# ProProject_2024__Wang01_2024-08-05.net
KiCad netlist of a schematic drawn in EasyEDA Pro
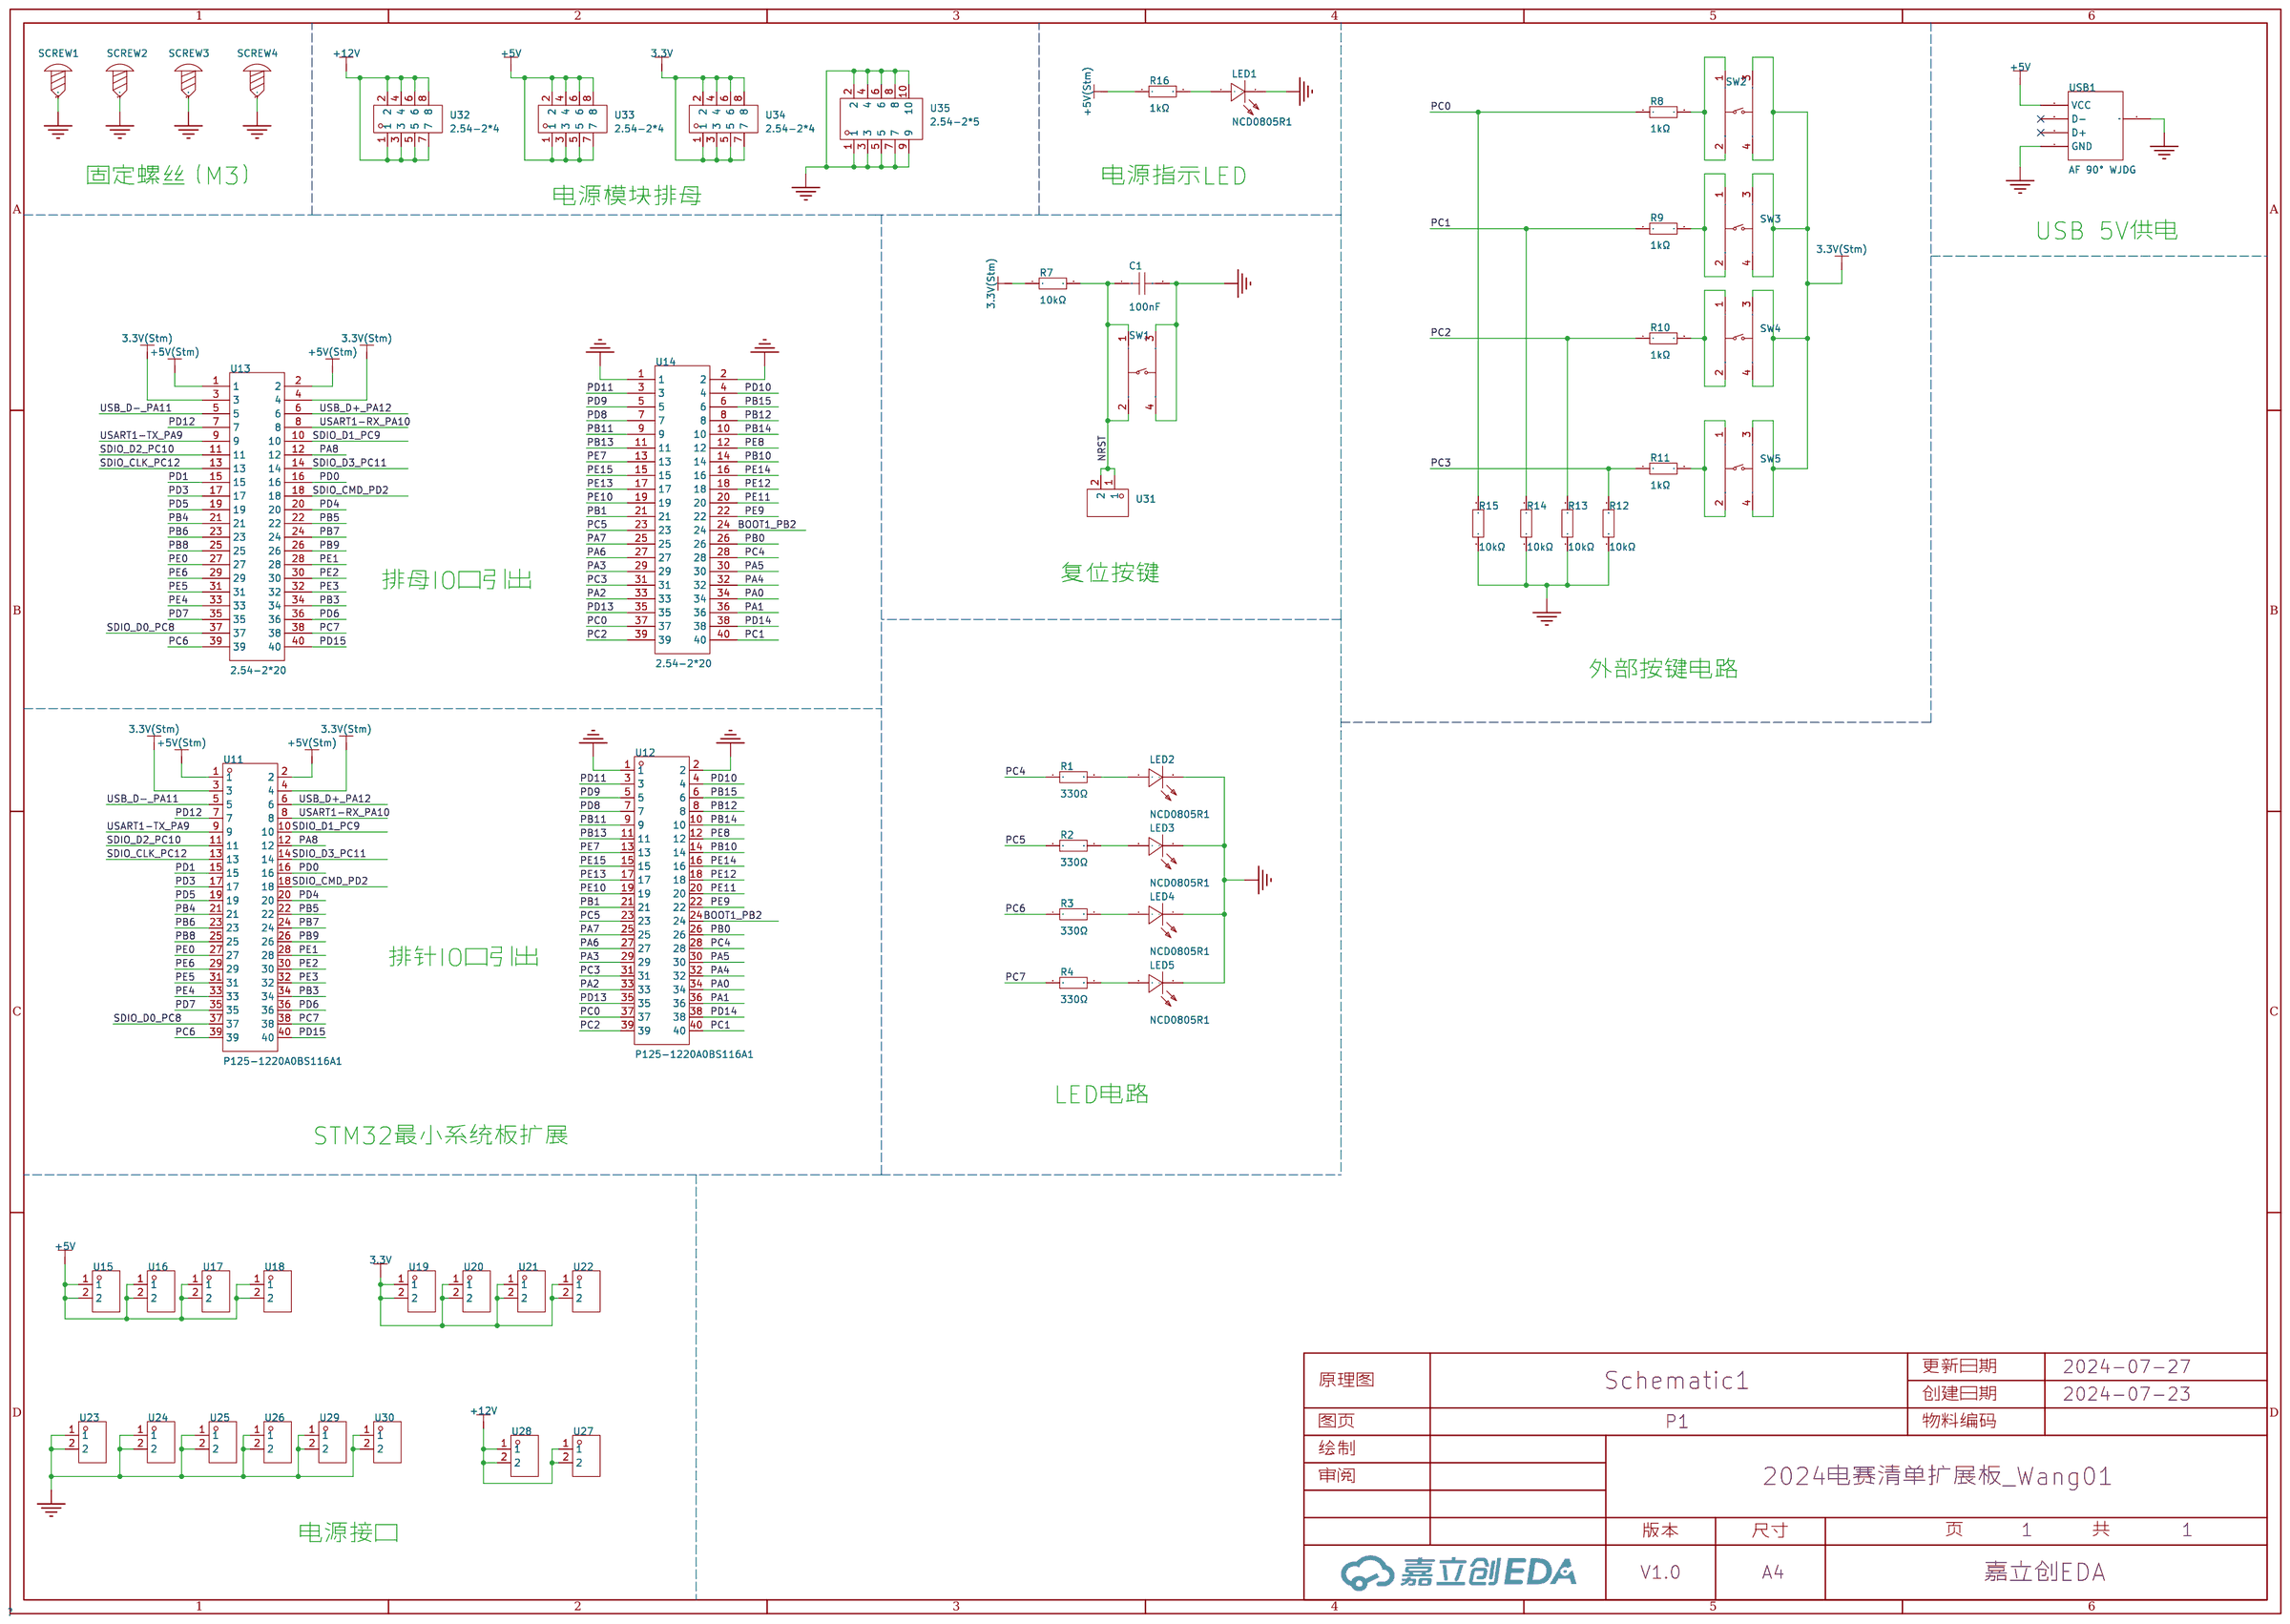
[diagram p0: schematic sheet]

(export (version "E")
  (design (tool "Eeschema 10.0.6"))
  (components
    (comp (ref "C1")
      (value "100nF")
      (footprint "easyedapro:C0603")
      (description "容值:100nF;精度:±10%;额定电压:50V;材质(温度系数):X7R;")
      (fields
        (field (name "Manufacturer Part") "CC0603KRX7R9BB104")
        (field (name "Manufacturer") "YAGEO(国巨)")
      )
      (libsource (lib "easyedapro") (part "CC0603KRX7R9BB104"))
    )
    (comp (ref "LED1")
      (value "NCD0805R1")
      (footprint "easyedapro:LED0805-R-RD")
      (fields (field (name "Manufacturer") "国星光电"))
      (libsource (lib "easyedapro") (part "FC-2012HRK-620D"))
    )
    (comp (ref "LED2")
      (value "NCD0805R1")
      (footprint "easyedapro:LED0805-R-RD")
      (fields (field (name "Manufacturer") "国星光电"))
      (libsource (lib "easyedapro") (part "FC-2012HRK-620D"))
    )
    (comp (ref "LED3")
      (value "NCD0805R1")
      (footprint "easyedapro:LED0805-R-RD")
      (fields (field (name "Manufacturer") "国星光电"))
      (libsource (lib "easyedapro") (part "FC-2012HRK-620D"))
    )
    (comp (ref "LED4")
      (value "NCD0805R1")
      (footprint "easyedapro:LED0805-R-RD")
      (fields (field (name "Manufacturer") "国星光电"))
      (libsource (lib "easyedapro") (part "FC-2012HRK-620D"))
    )
    (comp (ref "LED5")
      (value "NCD0805R1")
      (footprint "easyedapro:LED0805-R-RD")
      (fields (field (name "Manufacturer") "国星光电"))
      (libsource (lib "easyedapro") (part "FC-2012HRK-620D"))
    )
    (comp (ref "R1")
      (value "330Ω")
      (footprint "easyedapro:R0805")
      (description "电阻类型:厚膜电阻;阻值:330Ω;精度:±1%;功率:125mW;最大工作电压:150V;温度系数:±100ppm/°C;")
      (fields
        (field (name "Manufacturer Part") "0805W8F3300T5E")
        (field (name "Manufacturer") "UNI-ROYAL(厚声)")
      )
      (libsource (lib "easyedapro") (part "0805W8F3300T5E"))
    )
    (comp (ref "R2")
      (value "330Ω")
      (footprint "easyedapro:R0805")
      (description "电阻类型:厚膜电阻;阻值:330Ω;精度:±1%;功率:125mW;最大工作电压:150V;温度系数:±100ppm/°C;")
      (fields
        (field (name "Manufacturer Part") "0805W8F3300T5E")
        (field (name "Manufacturer") "UNI-ROYAL(厚声)")
      )
      (libsource (lib "easyedapro") (part "0805W8F3300T5E"))
    )
    (comp (ref "R3")
      (value "330Ω")
      (footprint "easyedapro:R0805")
      (description "电阻类型:厚膜电阻;阻值:330Ω;精度:±1%;功率:125mW;最大工作电压:150V;温度系数:±100ppm/°C;")
      (fields
        (field (name "Manufacturer Part") "0805W8F3300T5E")
        (field (name "Manufacturer") "UNI-ROYAL(厚声)")
      )
      (libsource (lib "easyedapro") (part "0805W8F3300T5E"))
    )
    (comp (ref "R4")
      (value "330Ω")
      (footprint "easyedapro:R0805")
      (description "电阻类型:厚膜电阻;阻值:330Ω;精度:±1%;功率:125mW;最大工作电压:150V;温度系数:±100ppm/°C;")
      (fields
        (field (name "Manufacturer Part") "0805W8F3300T5E")
        (field (name "Manufacturer") "UNI-ROYAL(厚声)")
      )
      (libsource (lib "easyedapro") (part "0805W8F3300T5E"))
    )
    (comp (ref "R7")
      (value "10kΩ")
      (footprint "easyedapro:R1206")
      (description "电阻类型:厚膜电阻;阻值:10kΩ;精度:±1%;功率:250mW;最大工作电压:200V;温度系数:±100ppm/°C;")
      (fields
        (field (name "Manufacturer Part") "1206W4F1002T5E")
        (field (name "Manufacturer") "UNI-ROYAL(厚声)")
      )
      (libsource (lib "easyedapro") (part "1206W4F1002T5E"))
    )
    (comp (ref "R8")
      (value "1kΩ")
      (footprint "easyedapro:R0805")
      (description "电阻类型:厚膜电阻;阻值:1kΩ;精度:±1%;功率:125mW;最大工作电压:150V;温度系数:±100ppm/°C;")
      (fields
        (field (name "Manufacturer Part") "0805W8F1001T5E")
        (field (name "Manufacturer") "UNI-ROYAL(厚声)")
      )
      (libsource (lib "easyedapro") (part "0805W8F1001T5E"))
    )
    (comp (ref "R9")
      (value "1kΩ")
      (footprint "easyedapro:R0805")
      (description "电阻类型:厚膜电阻;阻值:1kΩ;精度:±1%;功率:125mW;最大工作电压:150V;温度系数:±100ppm/°C;")
      (fields
        (field (name "Manufacturer Part") "0805W8F1001T5E")
        (field (name "Manufacturer") "UNI-ROYAL(厚声)")
      )
      (libsource (lib "easyedapro") (part "0805W8F1001T5E"))
    )
    (comp (ref "R10")
      (value "1kΩ")
      (footprint "easyedapro:R0805")
      (description "电阻类型:厚膜电阻;阻值:1kΩ;精度:±1%;功率:125mW;最大工作电压:150V;温度系数:±100ppm/°C;")
      (fields
        (field (name "Manufacturer Part") "0805W8F1001T5E")
        (field (name "Manufacturer") "UNI-ROYAL(厚声)")
      )
      (libsource (lib "easyedapro") (part "0805W8F1001T5E"))
    )
    (comp (ref "R11")
      (value "1kΩ")
      (footprint "easyedapro:R0805")
      (description "电阻类型:厚膜电阻;阻值:1kΩ;精度:±1%;功率:125mW;最大工作电压:150V;温度系数:±100ppm/°C;")
      (fields
        (field (name "Manufacturer Part") "0805W8F1001T5E")
        (field (name "Manufacturer") "UNI-ROYAL(厚声)")
      )
      (libsource (lib "easyedapro") (part "0805W8F1001T5E"))
    )
    (comp (ref "R12")
      (value "10kΩ")
      (footprint "easyedapro:R0805")
      (description "电阻类型:厚膜电阻;阻值:10kΩ;精度:±1%;功率:125mW;最大工作电压:150V;温度系数:±100ppm/°C;")
      (fields
        (field (name "Manufacturer Part") "0805W8F1002T5E")
        (field (name "Manufacturer") "UNI-ROYAL(厚声)")
      )
      (libsource (lib "easyedapro") (part "0805W8F1002T5E"))
    )
    (comp (ref "R13")
      (value "10kΩ")
      (footprint "easyedapro:R0805")
      (description "电阻类型:厚膜电阻;阻值:10kΩ;精度:±1%;功率:125mW;最大工作电压:150V;温度系数:±100ppm/°C;")
      (fields
        (field (name "Manufacturer Part") "0805W8F1002T5E")
        (field (name "Manufacturer") "UNI-ROYAL(厚声)")
      )
      (libsource (lib "easyedapro") (part "0805W8F1002T5E"))
    )
    (comp (ref "R14")
      (value "10kΩ")
      (footprint "easyedapro:R0805")
      (description "电阻类型:厚膜电阻;阻值:10kΩ;精度:±1%;功率:125mW;最大工作电压:150V;温度系数:±100ppm/°C;")
      (fields
        (field (name "Manufacturer Part") "0805W8F1002T5E")
        (field (name "Manufacturer") "UNI-ROYAL(厚声)")
      )
      (libsource (lib "easyedapro") (part "0805W8F1002T5E"))
    )
    (comp (ref "R15")
      (value "10kΩ")
      (footprint "easyedapro:R0805")
      (description "电阻类型:厚膜电阻;阻值:10kΩ;精度:±1%;功率:125mW;最大工作电压:150V;温度系数:±100ppm/°C;")
      (fields
        (field (name "Manufacturer Part") "0805W8F1002T5E")
        (field (name "Manufacturer") "UNI-ROYAL(厚声)")
      )
      (libsource (lib "easyedapro") (part "0805W8F1002T5E"))
    )
    (comp (ref "R16")
      (value "1kΩ")
      (footprint "easyedapro:R0603")
      (description "电阻类型:厚膜电阻;阻值:1kΩ;精度:±1%;功率:100mW;最大工作电压:75V;温度系数:±100ppm/°C;")
      (fields
        (field (name "Manufacturer Part") "0603WAF1001T5E")
        (field (name "Manufacturer") "UNI-ROYAL(厚声)")
      )
      (libsource (lib "easyedapro") (part "0603WAF1001T5E"))
    )
    (comp (ref "SCREW1")
      (value "~")
      (footprint "easyedapro:M3螺丝")
      (libsource (lib "easyedapro") (part "螺丝孔"))
    )
    (comp (ref "SCREW2")
      (value "~")
      (footprint "easyedapro:M3螺丝")
      (libsource (lib "easyedapro") (part "螺丝孔"))
    )
    (comp (ref "SCREW3")
      (value "~")
      (footprint "easyedapro:M3螺丝")
      (libsource (lib "easyedapro") (part "螺丝孔"))
    )
    (comp (ref "SCREW4")
      (value "~")
      (footprint "easyedapro:M3螺丝")
      (libsource (lib "easyedapro") (part "螺丝孔"))
    )
    (comp (ref "SW1")
      (value "TS665CJ")
      (footprint "easyedapro:SW-TH_4P-L6.0-W6.0-P4.50-LS6.5")
      (description "电路结构:单刀单掷;按钮形状:圆形按钮;安装方式:直插;开关长度:6mm;开关宽度:6mm;开关高度:5mm;触点电流:50mA;额定电压(DC):12V;带灯:-;机械寿命:-;")
      (fields (field (name "Manufacturer") "SHOU HAN(首韩)"))
      (libsource (lib "easyedapro") (part "TS665CJ"))
    )
    (comp (ref "SW2")
      (value "TS665CJ")
      (footprint "easyedapro:SW-TH_4P-L6.0-W6.0-P4.50-LS6.5")
      (description "电路结构:单刀单掷;按钮形状:圆形按钮;安装方式:直插;开关长度:6mm;开关宽度:6mm;开关高度:5mm;触点电流:50mA;额定电压(DC):12V;带灯:-;机械寿命:-;")
      (fields (field (name "Manufacturer") "SHOU HAN(首韩)"))
      (libsource (lib "easyedapro") (part "TS665CJ"))
    )
    (comp (ref "SW3")
      (value "TS665CJ")
      (footprint "easyedapro:SW-TH_4P-L6.0-W6.0-P4.50-LS6.5")
      (description "电路结构:单刀单掷;按钮形状:圆形按钮;安装方式:直插;开关长度:6mm;开关宽度:6mm;开关高度:5mm;触点电流:50mA;额定电压(DC):12V;带灯:-;机械寿命:-;")
      (fields (field (name "Manufacturer") "SHOU HAN(首韩)"))
      (libsource (lib "easyedapro") (part "TS665CJ"))
    )
    (comp (ref "SW4")
      (value "TS665CJ")
      (footprint "easyedapro:SW-TH_4P-L6.0-W6.0-P4.50-LS6.5")
      (description "电路结构:单刀单掷;按钮形状:圆形按钮;安装方式:直插;开关长度:6mm;开关宽度:6mm;开关高度:5mm;触点电流:50mA;额定电压(DC):12V;带灯:-;机械寿命:-;")
      (fields (field (name "Manufacturer") "SHOU HAN(首韩)"))
      (libsource (lib "easyedapro") (part "TS665CJ"))
    )
    (comp (ref "SW5")
      (value "TS665CJ")
      (footprint "easyedapro:SW-TH_4P-L6.0-W6.0-P4.50-LS6.5")
      (description "电路结构:单刀单掷;按钮形状:圆形按钮;安装方式:直插;开关长度:6mm;开关宽度:6mm;开关高度:5mm;触点电流:50mA;额定电压(DC):12V;带灯:-;机械寿命:-;")
      (fields (field (name "Manufacturer") "SHOU HAN(首韩)"))
      (libsource (lib "easyedapro") (part "TS665CJ"))
    )
    (comp (ref "U11")
      (value "P125-1220A0BS116A1")
      (footprint "easyedapro:HDR-TH_40P-P2.54-V-M-R2-C20-S2.54_10-97-7406")
      (fields (field (name "Manufacturer") "Yxcon(宇熙精密)"))
      (libsource (lib "easyedapro") (part "P125-1220A0BS116A1"))
    )
    (comp (ref "U12")
      (value "P125-1220A0BS116A1")
      (footprint "easyedapro:HDR-TH_40P-P2.54-V-M-R2-C20-S2.54_10-97-7406")
      (fields (field (name "Manufacturer") "Yxcon(宇熙精密)"))
      (libsource (lib "easyedapro") (part "P125-1220A0BS116A1"))
    )
    (comp (ref "U13")
      (value "2.54-2*20")
      (footprint "easyedapro:HDR-TH_40P-P2.54-V-F-R2-C20-S2.54")
      (fields (field (name "Manufacturer") "ZHOURI(洲日)"))
      (libsource (lib "easyedapro") (part "2.54-2*20"))
    )
    (comp (ref "U14")
      (value "2.54-2*20")
      (footprint "easyedapro:HDR-TH_40P-P2.54-V-F-R2-C20-S2.54")
      (fields (field (name "Manufacturer") "ZHOURI(洲日)"))
      (libsource (lib "easyedapro") (part "2.54-2*20"))
    )
    (comp (ref "U15")
      (value "KF301-5.0-2P")
      (footprint "easyedapro:CONN-TH_P5.00_KF301-5.0-2P")
      (fields (field (name "Manufacturer") "KEFA(科发)"))
      (libsource (lib "easyedapro") (part "KF301-5.0-2P"))
    )
    (comp (ref "U16")
      (value "KF301-5.0-2P")
      (footprint "easyedapro:CONN-TH_P5.00_KF301-5.0-2P")
      (fields (field (name "Manufacturer") "KEFA(科发)"))
      (libsource (lib "easyedapro") (part "KF301-5.0-2P"))
    )
    (comp (ref "U17")
      (value "KF301-5.0-2P")
      (footprint "easyedapro:CONN-TH_P5.00_KF301-5.0-2P")
      (fields (field (name "Manufacturer") "KEFA(科发)"))
      (libsource (lib "easyedapro") (part "KF301-5.0-2P"))
    )
    (comp (ref "U18")
      (value "KF301-5.0-2P")
      (footprint "easyedapro:CONN-TH_P5.00_KF301-5.0-2P")
      (fields (field (name "Manufacturer") "KEFA(科发)"))
      (libsource (lib "easyedapro") (part "KF301-5.0-2P"))
    )
    (comp (ref "U19")
      (value "KF301-5.0-2P")
      (footprint "easyedapro:CONN-TH_P5.00_KF301-5.0-2P")
      (fields (field (name "Manufacturer") "KEFA(科发)"))
      (libsource (lib "easyedapro") (part "KF301-5.0-2P"))
    )
    (comp (ref "U20")
      (value "KF301-5.0-2P")
      (footprint "easyedapro:CONN-TH_P5.00_KF301-5.0-2P")
      (fields (field (name "Manufacturer") "KEFA(科发)"))
      (libsource (lib "easyedapro") (part "KF301-5.0-2P"))
    )
    (comp (ref "U21")
      (value "KF301-5.0-2P")
      (footprint "easyedapro:CONN-TH_P5.00_KF301-5.0-2P")
      (fields (field (name "Manufacturer") "KEFA(科发)"))
      (libsource (lib "easyedapro") (part "KF301-5.0-2P"))
    )
    (comp (ref "U22")
      (value "KF301-5.0-2P")
      (footprint "easyedapro:CONN-TH_P5.00_KF301-5.0-2P")
      (fields (field (name "Manufacturer") "KEFA(科发)"))
      (libsource (lib "easyedapro") (part "KF301-5.0-2P"))
    )
    (comp (ref "U23")
      (value "KF301-5.0-2P")
      (footprint "easyedapro:CONN-TH_P5.00_KF301-5.0-2P")
      (fields (field (name "Manufacturer") "KEFA(科发)"))
      (libsource (lib "easyedapro") (part "KF301-5.0-2P"))
    )
    (comp (ref "U24")
      (value "KF301-5.0-2P")
      (footprint "easyedapro:CONN-TH_P5.00_KF301-5.0-2P")
      (fields (field (name "Manufacturer") "KEFA(科发)"))
      (libsource (lib "easyedapro") (part "KF301-5.0-2P"))
    )
    (comp (ref "U25")
      (value "KF301-5.0-2P")
      (footprint "easyedapro:CONN-TH_P5.00_KF301-5.0-2P")
      (fields (field (name "Manufacturer") "KEFA(科发)"))
      (libsource (lib "easyedapro") (part "KF301-5.0-2P"))
    )
    (comp (ref "U26")
      (value "KF301-5.0-2P")
      (footprint "easyedapro:CONN-TH_P5.00_KF301-5.0-2P")
      (fields (field (name "Manufacturer") "KEFA(科发)"))
      (libsource (lib "easyedapro") (part "KF301-5.0-2P"))
    )
    (comp (ref "U27")
      (value "KF301-5.0-2P")
      (footprint "easyedapro:CONN-TH_P5.00_KF301-5.0-2P")
      (fields (field (name "Manufacturer") "KEFA(科发)"))
      (libsource (lib "easyedapro") (part "KF301-5.0-2P"))
    )
    (comp (ref "U28")
      (value "KF301-5.0-2P")
      (footprint "easyedapro:CONN-TH_P5.00_KF301-5.0-2P")
      (fields (field (name "Manufacturer") "KEFA(科发)"))
      (libsource (lib "easyedapro") (part "KF301-5.0-2P"))
    )
    (comp (ref "U29")
      (value "KF301-5.0-2P")
      (footprint "easyedapro:CONN-TH_P5.00_KF301-5.0-2P")
      (fields (field (name "Manufacturer") "KEFA(科发)"))
      (libsource (lib "easyedapro") (part "KF301-5.0-2P"))
    )
    (comp (ref "U30")
      (value "KF301-5.0-2P")
      (footprint "easyedapro:CONN-TH_P5.00_KF301-5.0-2P")
      (fields (field (name "Manufacturer") "KEFA(科发)"))
      (libsource (lib "easyedapro") (part "KF301-5.0-2P"))
    )
    (comp (ref "U31")
      (value "KF301-5.0-2P")
      (footprint "easyedapro:CONN-TH_P5.00_KF301-5.0-2P")
      (fields (field (name "Manufacturer") "KEFA(科发)"))
      (libsource (lib "easyedapro") (part "KF301-5.0-2P"))
    )
    (comp (ref "U32")
      (value "2.54-2*4")
      (footprint "easyedapro:HDR-TH_8P-P2.54-V-F-R2-C4-S2.54")
      (fields (field (name "Manufacturer") "ZHOURI(洲日)"))
      (libsource (lib "easyedapro") (part "2.54-2*4"))
    )
    (comp (ref "U33")
      (value "2.54-2*4")
      (footprint "easyedapro:HDR-TH_8P-P2.54-V-F-R2-C4-S2.54")
      (fields (field (name "Manufacturer") "ZHOURI(洲日)"))
      (libsource (lib "easyedapro") (part "2.54-2*4"))
    )
    (comp (ref "U34")
      (value "2.54-2*4")
      (footprint "easyedapro:HDR-TH_8P-P2.54-V-F-R2-C4-S2.54")
      (fields (field (name "Manufacturer") "ZHOURI(洲日)"))
      (libsource (lib "easyedapro") (part "2.54-2*4"))
    )
    (comp (ref "U35")
      (value "2.54-2*5")
      (footprint "easyedapro:HDR-TH_10P-P2.54-V-F-R2-C5-S2.54")
      (fields (field (name "Manufacturer") "ZHOURI(洲日)"))
      (libsource (lib "easyedapro") (part "2.54-2*5"))
    )
    (comp (ref "USB1")
      (value "AF 90° WJDG")
      (footprint "easyedapro:USB-A-TH_AF-WJDG")
      (description "连接器类型:Type-A;标准:USB 2.0;公母:母;端口数量:1;触点数量:4P;安装方式:弯插;额定电流 - 电源:1.5A;工作温度范围:-25°C~+85°C;")
      (fields (field (name "Manufacturer") "SHOU HAN(首韩)"))
      (libsource (lib "easyedapro") (part "AF 90° WJDG"))
    )
  )
  (nets
    (net (code "1") (name "+5V") (class "Default")
      (node (ref "U15") (pin "1") (pinfunction "1_1") (pintype "unspecified"))
      (node (ref "U15") (pin "2") (pinfunction "2_2") (pintype "unspecified"))
      (node (ref "U16") (pin "1") (pinfunction "1_1") (pintype "unspecified"))
      (node (ref "U16") (pin "2") (pinfunction "2_2") (pintype "unspecified"))
      (node (ref "U17") (pin "1") (pinfunction "1_1") (pintype "unspecified"))
      (node (ref "U17") (pin "2") (pinfunction "2_2") (pintype "unspecified"))
      (node (ref "U18") (pin "1") (pinfunction "1_1") (pintype "unspecified"))
      (node (ref "U18") (pin "2") (pinfunction "2_2") (pintype "unspecified"))
      (node (ref "U33") (pin "1") (pinfunction "1_1") (pintype "unspecified"))
      (node (ref "U33") (pin "2") (pinfunction "2_2") (pintype "unspecified"))
      (node (ref "U33") (pin "3") (pinfunction "3_3") (pintype "unspecified"))
      (node (ref "U33") (pin "4") (pinfunction "4_4") (pintype "unspecified"))
      (node (ref "U33") (pin "5") (pinfunction "5_5") (pintype "unspecified"))
      (node (ref "U33") (pin "6") (pinfunction "6_6") (pintype "unspecified"))
      (node (ref "U33") (pin "7") (pinfunction "7_7") (pintype "unspecified"))
      (node (ref "U33") (pin "8") (pinfunction "8_8") (pintype "unspecified"))
      (node (ref "USB1") (pin "1") (pinfunction "VCC_1") (pintype "input"))
    )
    (net (code "2") (name "+5V(Stm)") (class "Default")
      (node (ref "R16") (pin "1") (pinfunction "1_1") (pintype "input"))
      (node (ref "U11") (pin "1") (pinfunction "1_1") (pintype "unspecified"))
      (node (ref "U11") (pin "2") (pinfunction "2_2") (pintype "unspecified"))
      (node (ref "U13") (pin "1") (pinfunction "1_1") (pintype "unspecified"))
      (node (ref "U13") (pin "2") (pinfunction "2_2") (pintype "unspecified"))
    )
    (net (code "3") (name "+12V") (class "Default")
      (node (ref "U27") (pin "1") (pinfunction "1_1") (pintype "unspecified"))
      (node (ref "U27") (pin "2") (pinfunction "2_2") (pintype "unspecified"))
      (node (ref "U28") (pin "1") (pinfunction "1_1") (pintype "unspecified"))
      (node (ref "U28") (pin "2") (pinfunction "2_2") (pintype "unspecified"))
      (node (ref "U32") (pin "1") (pinfunction "1_1") (pintype "unspecified"))
      (node (ref "U32") (pin "2") (pinfunction "2_2") (pintype "unspecified"))
      (node (ref "U32") (pin "3") (pinfunction "3_3") (pintype "unspecified"))
      (node (ref "U32") (pin "4") (pinfunction "4_4") (pintype "unspecified"))
      (node (ref "U32") (pin "5") (pinfunction "5_5") (pintype "unspecified"))
      (node (ref "U32") (pin "6") (pinfunction "6_6") (pintype "unspecified"))
      (node (ref "U32") (pin "7") (pinfunction "7_7") (pintype "unspecified"))
      (node (ref "U32") (pin "8") (pinfunction "8_8") (pintype "unspecified"))
    )
    (net (code "4") (name "/BOOT1_PB2") (class "Default")
      (node (ref "U12") (pin "24") (pinfunction "24_24") (pintype "unspecified"))
      (node (ref "U14") (pin "24") (pinfunction "24_24") (pintype "unspecified"))
    )
    (net (code "5") (name "/NRST") (class "Default")
      (node (ref "C1") (pin "1") (pinfunction "1_1") (pintype "unspecified"))
      (node (ref "R7") (pin "2") (pinfunction "2_2") (pintype "input"))
      (node (ref "SW1") (pin "1") (pinfunction "A_1") (pintype "unspecified"))
      (node (ref "SW1") (pin "2") (pinfunction "B_2") (pintype "unspecified"))
      (node (ref "U31") (pin "1") (pinfunction "1_1") (pintype "unspecified"))
      (node (ref "U31") (pin "2") (pinfunction "2_2") (pintype "unspecified"))
    )
    (net (code "6") (name "/PA0") (class "Default")
      (node (ref "U12") (pin "34") (pinfunction "34_34") (pintype "unspecified"))
      (node (ref "U14") (pin "34") (pinfunction "34_34") (pintype "unspecified"))
    )
    (net (code "7") (name "/PA1") (class "Default")
      (node (ref "U12") (pin "36") (pinfunction "36_36") (pintype "unspecified"))
      (node (ref "U14") (pin "36") (pinfunction "36_36") (pintype "unspecified"))
    )
    (net (code "8") (name "/PA2") (class "Default")
      (node (ref "U12") (pin "33") (pinfunction "33_33") (pintype "unspecified"))
      (node (ref "U14") (pin "33") (pinfunction "33_33") (pintype "unspecified"))
    )
    (net (code "9") (name "/PA3") (class "Default")
      (node (ref "U12") (pin "29") (pinfunction "29_29") (pintype "unspecified"))
      (node (ref "U14") (pin "29") (pinfunction "29_29") (pintype "unspecified"))
    )
    (net (code "10") (name "/PA4") (class "Default")
      (node (ref "U12") (pin "32") (pinfunction "32_32") (pintype "unspecified"))
      (node (ref "U14") (pin "32") (pinfunction "32_32") (pintype "unspecified"))
    )
    (net (code "11") (name "/PA5") (class "Default")
      (node (ref "U12") (pin "30") (pinfunction "30_30") (pintype "unspecified"))
      (node (ref "U14") (pin "30") (pinfunction "30_30") (pintype "unspecified"))
    )
    (net (code "12") (name "/PA6") (class "Default")
      (node (ref "U12") (pin "27") (pinfunction "27_27") (pintype "unspecified"))
      (node (ref "U14") (pin "27") (pinfunction "27_27") (pintype "unspecified"))
    )
    (net (code "13") (name "/PA7") (class "Default")
      (node (ref "U12") (pin "25") (pinfunction "25_25") (pintype "unspecified"))
      (node (ref "U14") (pin "25") (pinfunction "25_25") (pintype "unspecified"))
    )
    (net (code "14") (name "/PA8") (class "Default")
      (node (ref "U11") (pin "12") (pinfunction "12_12") (pintype "unspecified"))
      (node (ref "U13") (pin "12") (pinfunction "12_12") (pintype "unspecified"))
    )
    (net (code "15") (name "/PB0") (class "Default")
      (node (ref "U12") (pin "26") (pinfunction "26_26") (pintype "unspecified"))
      (node (ref "U14") (pin "26") (pinfunction "26_26") (pintype "unspecified"))
    )
    (net (code "16") (name "/PB1") (class "Default")
      (node (ref "U12") (pin "21") (pinfunction "21_21") (pintype "unspecified"))
      (node (ref "U14") (pin "21") (pinfunction "21_21") (pintype "unspecified"))
    )
    (net (code "17") (name "/PB3") (class "Default")
      (node (ref "U11") (pin "34") (pinfunction "34_34") (pintype "unspecified"))
      (node (ref "U13") (pin "34") (pinfunction "34_34") (pintype "unspecified"))
    )
    (net (code "18") (name "/PB4") (class "Default")
      (node (ref "U11") (pin "21") (pinfunction "21_21") (pintype "unspecified"))
      (node (ref "U13") (pin "21") (pinfunction "21_21") (pintype "unspecified"))
    )
    (net (code "19") (name "/PB5") (class "Default")
      (node (ref "U11") (pin "22") (pinfunction "22_22") (pintype "unspecified"))
      (node (ref "U13") (pin "22") (pinfunction "22_22") (pintype "unspecified"))
    )
    (net (code "20") (name "/PB6") (class "Default")
      (node (ref "U11") (pin "23") (pinfunction "23_23") (pintype "unspecified"))
      (node (ref "U13") (pin "23") (pinfunction "23_23") (pintype "unspecified"))
    )
    (net (code "21") (name "/PB7") (class "Default")
      (node (ref "U11") (pin "24") (pinfunction "24_24") (pintype "unspecified"))
      (node (ref "U13") (pin "24") (pinfunction "24_24") (pintype "unspecified"))
    )
    (net (code "22") (name "/PB8") (class "Default")
      (node (ref "U11") (pin "25") (pinfunction "25_25") (pintype "unspecified"))
      (node (ref "U13") (pin "25") (pinfunction "25_25") (pintype "unspecified"))
    )
    (net (code "23") (name "/PB9") (class "Default")
      (node (ref "U11") (pin "26") (pinfunction "26_26") (pintype "unspecified"))
      (node (ref "U13") (pin "26") (pinfunction "26_26") (pintype "unspecified"))
    )
    (net (code "24") (name "/PB10") (class "Default")
      (node (ref "U12") (pin "14") (pinfunction "14_14") (pintype "unspecified"))
      (node (ref "U14") (pin "14") (pinfunction "14_14") (pintype "unspecified"))
    )
    (net (code "25") (name "/PB11") (class "Default")
      (node (ref "U12") (pin "9") (pinfunction "9_9") (pintype "unspecified"))
      (node (ref "U14") (pin "9") (pinfunction "9_9") (pintype "unspecified"))
    )
    (net (code "26") (name "/PB12") (class "Default")
      (node (ref "U12") (pin "8") (pinfunction "8_8") (pintype "unspecified"))
      (node (ref "U14") (pin "8") (pinfunction "8_8") (pintype "unspecified"))
    )
    (net (code "27") (name "/PB13") (class "Default")
      (node (ref "U12") (pin "11") (pinfunction "11_11") (pintype "unspecified"))
      (node (ref "U14") (pin "11") (pinfunction "11_11") (pintype "unspecified"))
    )
    (net (code "28") (name "/PB14") (class "Default")
      (node (ref "U12") (pin "10") (pinfunction "10_10") (pintype "unspecified"))
      (node (ref "U14") (pin "10") (pinfunction "10_10") (pintype "unspecified"))
    )
    (net (code "29") (name "/PB15") (class "Default")
      (node (ref "U12") (pin "6") (pinfunction "6_6") (pintype "unspecified"))
      (node (ref "U14") (pin "6") (pinfunction "6_6") (pintype "unspecified"))
    )
    (net (code "30") (name "/PC0") (class "Default")
      (node (ref "R15") (pin "2") (pinfunction "2_2") (pintype "input"))
      (node (ref "R8") (pin "1") (pinfunction "1_1") (pintype "input"))
      (node (ref "U12") (pin "37") (pinfunction "37_37") (pintype "unspecified"))
      (node (ref "U14") (pin "37") (pinfunction "37_37") (pintype "unspecified"))
    )
    (net (code "31") (name "/PC1") (class "Default")
      (node (ref "R14") (pin "2") (pinfunction "2_2") (pintype "input"))
      (node (ref "R9") (pin "1") (pinfunction "1_1") (pintype "input"))
      (node (ref "U12") (pin "40") (pinfunction "40_40") (pintype "unspecified"))
      (node (ref "U14") (pin "40") (pinfunction "40_40") (pintype "unspecified"))
    )
    (net (code "32") (name "/PC2") (class "Default")
      (node (ref "R10") (pin "1") (pinfunction "1_1") (pintype "input"))
      (node (ref "R13") (pin "2") (pinfunction "2_2") (pintype "input"))
      (node (ref "U12") (pin "39") (pinfunction "39_39") (pintype "unspecified"))
      (node (ref "U14") (pin "39") (pinfunction "39_39") (pintype "unspecified"))
    )
    (net (code "33") (name "/PC3") (class "Default")
      (node (ref "R11") (pin "1") (pinfunction "1_1") (pintype "input"))
      (node (ref "R12") (pin "2") (pinfunction "2_2") (pintype "input"))
      (node (ref "U12") (pin "31") (pinfunction "31_31") (pintype "unspecified"))
      (node (ref "U14") (pin "31") (pinfunction "31_31") (pintype "unspecified"))
    )
    (net (code "34") (name "/PC4") (class "Default")
      (node (ref "R1") (pin "1") (pinfunction "1_1") (pintype "input"))
      (node (ref "U12") (pin "28") (pinfunction "28_28") (pintype "unspecified"))
      (node (ref "U14") (pin "28") (pinfunction "28_28") (pintype "unspecified"))
    )
    (net (code "35") (name "/PC5") (class "Default")
      (node (ref "R2") (pin "1") (pinfunction "1_1") (pintype "input"))
      (node (ref "U12") (pin "23") (pinfunction "23_23") (pintype "unspecified"))
      (node (ref "U14") (pin "23") (pinfunction "23_23") (pintype "unspecified"))
    )
    (net (code "36") (name "/PC6") (class "Default")
      (node (ref "R3") (pin "1") (pinfunction "1_1") (pintype "input"))
      (node (ref "U11") (pin "39") (pinfunction "39_39") (pintype "unspecified"))
      (node (ref "U13") (pin "39") (pinfunction "39_39") (pintype "unspecified"))
    )
    (net (code "37") (name "/PC7") (class "Default")
      (node (ref "R4") (pin "1") (pinfunction "1_1") (pintype "input"))
      (node (ref "U11") (pin "38") (pinfunction "38_38") (pintype "unspecified"))
      (node (ref "U13") (pin "38") (pinfunction "38_38") (pintype "unspecified"))
    )
    (net (code "38") (name "/PD0") (class "Default")
      (node (ref "U11") (pin "16") (pinfunction "16_16") (pintype "unspecified"))
      (node (ref "U13") (pin "16") (pinfunction "16_16") (pintype "unspecified"))
    )
    (net (code "39") (name "/PD1") (class "Default")
      (node (ref "U11") (pin "15") (pinfunction "15_15") (pintype "unspecified"))
      (node (ref "U13") (pin "15") (pinfunction "15_15") (pintype "unspecified"))
    )
    (net (code "40") (name "/PD3") (class "Default")
      (node (ref "U11") (pin "17") (pinfunction "17_17") (pintype "unspecified"))
      (node (ref "U13") (pin "17") (pinfunction "17_17") (pintype "unspecified"))
    )
    (net (code "41") (name "/PD4") (class "Default")
      (node (ref "U11") (pin "20") (pinfunction "20_20") (pintype "unspecified"))
      (node (ref "U13") (pin "20") (pinfunction "20_20") (pintype "unspecified"))
    )
    (net (code "42") (name "/PD5") (class "Default")
      (node (ref "U11") (pin "19") (pinfunction "19_19") (pintype "unspecified"))
      (node (ref "U13") (pin "19") (pinfunction "19_19") (pintype "unspecified"))
    )
    (net (code "43") (name "/PD6") (class "Default")
      (node (ref "U11") (pin "36") (pinfunction "36_36") (pintype "unspecified"))
      (node (ref "U13") (pin "36") (pinfunction "36_36") (pintype "unspecified"))
    )
    (net (code "44") (name "/PD7") (class "Default")
      (node (ref "U11") (pin "35") (pinfunction "35_35") (pintype "unspecified"))
      (node (ref "U13") (pin "35") (pinfunction "35_35") (pintype "unspecified"))
    )
    (net (code "45") (name "/PD8") (class "Default")
      (node (ref "U12") (pin "7") (pinfunction "7_7") (pintype "unspecified"))
      (node (ref "U14") (pin "7") (pinfunction "7_7") (pintype "unspecified"))
    )
    (net (code "46") (name "/PD9") (class "Default")
      (node (ref "U12") (pin "5") (pinfunction "5_5") (pintype "unspecified"))
      (node (ref "U14") (pin "5") (pinfunction "5_5") (pintype "unspecified"))
    )
    (net (code "47") (name "/PD10") (class "Default")
      (node (ref "U12") (pin "4") (pinfunction "4_4") (pintype "unspecified"))
      (node (ref "U14") (pin "4") (pinfunction "4_4") (pintype "unspecified"))
    )
    (net (code "48") (name "/PD11") (class "Default")
      (node (ref "U12") (pin "3") (pinfunction "3_3") (pintype "unspecified"))
      (node (ref "U14") (pin "3") (pinfunction "3_3") (pintype "unspecified"))
    )
    (net (code "49") (name "/PD12") (class "Default")
      (node (ref "U11") (pin "7") (pinfunction "7_7") (pintype "unspecified"))
      (node (ref "U13") (pin "7") (pinfunction "7_7") (pintype "unspecified"))
    )
    (net (code "50") (name "/PD13") (class "Default")
      (node (ref "U12") (pin "35") (pinfunction "35_35") (pintype "unspecified"))
      (node (ref "U14") (pin "35") (pinfunction "35_35") (pintype "unspecified"))
    )
    (net (code "51") (name "/PD14") (class "Default")
      (node (ref "U12") (pin "38") (pinfunction "38_38") (pintype "unspecified"))
      (node (ref "U14") (pin "38") (pinfunction "38_38") (pintype "unspecified"))
    )
    (net (code "52") (name "/PD15") (class "Default")
      (node (ref "U11") (pin "40") (pinfunction "40_40") (pintype "unspecified"))
      (node (ref "U13") (pin "40") (pinfunction "40_40") (pintype "unspecified"))
    )
    (net (code "53") (name "/PE0") (class "Default")
      (node (ref "U11") (pin "27") (pinfunction "27_27") (pintype "unspecified"))
      (node (ref "U13") (pin "27") (pinfunction "27_27") (pintype "unspecified"))
    )
    (net (code "54") (name "/PE1") (class "Default")
      (node (ref "U11") (pin "28") (pinfunction "28_28") (pintype "unspecified"))
      (node (ref "U13") (pin "28") (pinfunction "28_28") (pintype "unspecified"))
    )
    (net (code "55") (name "/PE2") (class "Default")
      (node (ref "U11") (pin "30") (pinfunction "30_30") (pintype "unspecified"))
      (node (ref "U13") (pin "30") (pinfunction "30_30") (pintype "unspecified"))
    )
    (net (code "56") (name "/PE3") (class "Default")
      (node (ref "U11") (pin "32") (pinfunction "32_32") (pintype "unspecified"))
      (node (ref "U13") (pin "32") (pinfunction "32_32") (pintype "unspecified"))
    )
    (net (code "57") (name "/PE4") (class "Default")
      (node (ref "U11") (pin "33") (pinfunction "33_33") (pintype "unspecified"))
      (node (ref "U13") (pin "33") (pinfunction "33_33") (pintype "unspecified"))
    )
    (net (code "58") (name "/PE5") (class "Default")
      (node (ref "U11") (pin "31") (pinfunction "31_31") (pintype "unspecified"))
      (node (ref "U13") (pin "31") (pinfunction "31_31") (pintype "unspecified"))
    )
    (net (code "59") (name "/PE6") (class "Default")
      (node (ref "U11") (pin "29") (pinfunction "29_29") (pintype "unspecified"))
      (node (ref "U13") (pin "29") (pinfunction "29_29") (pintype "unspecified"))
    )
    (net (code "60") (name "/PE7") (class "Default")
      (node (ref "U12") (pin "13") (pinfunction "13_13") (pintype "unspecified"))
      (node (ref "U14") (pin "13") (pinfunction "13_13") (pintype "unspecified"))
    )
    (net (code "61") (name "/PE8") (class "Default")
      (node (ref "U12") (pin "12") (pinfunction "12_12") (pintype "unspecified"))
      (node (ref "U14") (pin "12") (pinfunction "12_12") (pintype "unspecified"))
    )
    (net (code "62") (name "/PE9") (class "Default")
      (node (ref "U12") (pin "22") (pinfunction "22_22") (pintype "unspecified"))
      (node (ref "U14") (pin "22") (pinfunction "22_22") (pintype "unspecified"))
    )
    (net (code "63") (name "/PE10") (class "Default")
      (node (ref "U12") (pin "19") (pinfunction "19_19") (pintype "unspecified"))
      (node (ref "U14") (pin "19") (pinfunction "19_19") (pintype "unspecified"))
    )
    (net (code "64") (name "/PE11") (class "Default")
      (node (ref "U12") (pin "20") (pinfunction "20_20") (pintype "unspecified"))
      (node (ref "U14") (pin "20") (pinfunction "20_20") (pintype "unspecified"))
    )
    (net (code "65") (name "/PE12") (class "Default")
      (node (ref "U12") (pin "18") (pinfunction "18_18") (pintype "unspecified"))
      (node (ref "U14") (pin "18") (pinfunction "18_18") (pintype "unspecified"))
    )
    (net (code "66") (name "/PE13") (class "Default")
      (node (ref "U12") (pin "17") (pinfunction "17_17") (pintype "unspecified"))
      (node (ref "U14") (pin "17") (pinfunction "17_17") (pintype "unspecified"))
    )
    (net (code "67") (name "/PE14") (class "Default")
      (node (ref "U12") (pin "16") (pinfunction "16_16") (pintype "unspecified"))
      (node (ref "U14") (pin "16") (pinfunction "16_16") (pintype "unspecified"))
    )
    (net (code "68") (name "/PE15") (class "Default")
      (node (ref "U12") (pin "15") (pinfunction "15_15") (pintype "unspecified"))
      (node (ref "U14") (pin "15") (pinfunction "15_15") (pintype "unspecified"))
    )
    (net (code "69") (name "/SDIO_CLK_PC12") (class "Default")
      (node (ref "U11") (pin "13") (pinfunction "13_13") (pintype "unspecified"))
      (node (ref "U13") (pin "13") (pinfunction "13_13") (pintype "unspecified"))
    )
    (net (code "70") (name "/SDIO_CMD_PD2") (class "Default")
      (node (ref "U11") (pin "18") (pinfunction "18_18") (pintype "unspecified"))
      (node (ref "U13") (pin "18") (pinfunction "18_18") (pintype "unspecified"))
    )
    (net (code "71") (name "/SDIO_D0_PC8") (class "Default")
      (node (ref "U11") (pin "37") (pinfunction "37_37") (pintype "unspecified"))
      (node (ref "U13") (pin "37") (pinfunction "37_37") (pintype "unspecified"))
    )
    (net (code "72") (name "/SDIO_D1_PC9") (class "Default")
      (node (ref "U11") (pin "10") (pinfunction "10_10") (pintype "unspecified"))
      (node (ref "U13") (pin "10") (pinfunction "10_10") (pintype "unspecified"))
    )
    (net (code "73") (name "/SDIO_D2_PC10") (class "Default")
      (node (ref "U11") (pin "11") (pinfunction "11_11") (pintype "unspecified"))
      (node (ref "U13") (pin "11") (pinfunction "11_11") (pintype "unspecified"))
    )
    (net (code "74") (name "/SDIO_D3_PC11") (class "Default")
      (node (ref "U11") (pin "14") (pinfunction "14_14") (pintype "unspecified"))
      (node (ref "U13") (pin "14") (pinfunction "14_14") (pintype "unspecified"))
    )
    (net (code "75") (name "/USART1-RX_PA10") (class "Default")
      (node (ref "U11") (pin "8") (pinfunction "8_8") (pintype "unspecified"))
      (node (ref "U13") (pin "8") (pinfunction "8_8") (pintype "unspecified"))
    )
    (net (code "76") (name "/USART1-TX_PA9") (class "Default")
      (node (ref "U11") (pin "9") (pinfunction "9_9") (pintype "unspecified"))
      (node (ref "U13") (pin "9") (pinfunction "9_9") (pintype "unspecified"))
    )
    (net (code "77") (name "/USB_D+_PA12") (class "Default")
      (node (ref "U11") (pin "6") (pinfunction "6_6") (pintype "unspecified"))
      (node (ref "U13") (pin "6") (pinfunction "6_6") (pintype "unspecified"))
    )
    (net (code "78") (name "/USB_D-_PA11") (class "Default")
      (node (ref "U11") (pin "5") (pinfunction "5_5") (pintype "unspecified"))
      (node (ref "U13") (pin "5") (pinfunction "5_5") (pintype "unspecified"))
    )
    (net (code "79") (name "3.3V") (class "Default")
      (node (ref "U19") (pin "1") (pinfunction "1_1") (pintype "unspecified"))
      (node (ref "U19") (pin "2") (pinfunction "2_2") (pintype "unspecified"))
      (node (ref "U20") (pin "1") (pinfunction "1_1") (pintype "unspecified"))
      (node (ref "U20") (pin "2") (pinfunction "2_2") (pintype "unspecified"))
      (node (ref "U21") (pin "1") (pinfunction "1_1") (pintype "unspecified"))
      (node (ref "U21") (pin "2") (pinfunction "2_2") (pintype "unspecified"))
      (node (ref "U22") (pin "1") (pinfunction "1_1") (pintype "unspecified"))
      (node (ref "U22") (pin "2") (pinfunction "2_2") (pintype "unspecified"))
      (node (ref "U34") (pin "1") (pinfunction "1_1") (pintype "unspecified"))
      (node (ref "U34") (pin "2") (pinfunction "2_2") (pintype "unspecified"))
      (node (ref "U34") (pin "3") (pinfunction "3_3") (pintype "unspecified"))
      (node (ref "U34") (pin "4") (pinfunction "4_4") (pintype "unspecified"))
      (node (ref "U34") (pin "5") (pinfunction "5_5") (pintype "unspecified"))
      (node (ref "U34") (pin "6") (pinfunction "6_6") (pintype "unspecified"))
      (node (ref "U34") (pin "7") (pinfunction "7_7") (pintype "unspecified"))
      (node (ref "U34") (pin "8") (pinfunction "8_8") (pintype "unspecified"))
    )
    (net (code "80") (name "3.3V(Stm)") (class "Default")
      (node (ref "R7") (pin "1") (pinfunction "1_1") (pintype "input"))
      (node (ref "SW2") (pin "3") (pinfunction "C_3") (pintype "unspecified"))
      (node (ref "SW2") (pin "4") (pinfunction "D_4") (pintype "unspecified"))
      (node (ref "SW3") (pin "3") (pinfunction "C_3") (pintype "unspecified"))
      (node (ref "SW3") (pin "4") (pinfunction "D_4") (pintype "unspecified"))
      (node (ref "SW4") (pin "3") (pinfunction "C_3") (pintype "unspecified"))
      (node (ref "SW4") (pin "4") (pinfunction "D_4") (pintype "unspecified"))
      (node (ref "SW5") (pin "3") (pinfunction "C_3") (pintype "unspecified"))
      (node (ref "SW5") (pin "4") (pinfunction "D_4") (pintype "unspecified"))
      (node (ref "U11") (pin "3") (pinfunction "3_3") (pintype "unspecified"))
      (node (ref "U11") (pin "4") (pinfunction "4_4") (pintype "unspecified"))
      (node (ref "U13") (pin "3") (pinfunction "3_3") (pintype "unspecified"))
      (node (ref "U13") (pin "4") (pinfunction "4_4") (pintype "unspecified"))
    )
    (net (code "81") (name "GND") (class "Default")
      (node (ref "C1") (pin "2") (pinfunction "2_2") (pintype "unspecified"))
      (node (ref "LED1") (pin "2") (pinfunction "-_2") (pintype "unspecified"))
      (node (ref "LED2") (pin "2") (pinfunction "-_2") (pintype "unspecified"))
      (node (ref "LED3") (pin "2") (pinfunction "-_2") (pintype "unspecified"))
      (node (ref "LED4") (pin "2") (pinfunction "-_2") (pintype "unspecified"))
      (node (ref "LED5") (pin "2") (pinfunction "-_2") (pintype "unspecified"))
      (node (ref "R12") (pin "1") (pinfunction "1_1") (pintype "input"))
      (node (ref "R13") (pin "1") (pinfunction "1_1") (pintype "input"))
      (node (ref "R14") (pin "1") (pinfunction "1_1") (pintype "input"))
      (node (ref "R15") (pin "1") (pinfunction "1_1") (pintype "input"))
      (node (ref "SCREW1") (pin "1") (pinfunction "1_1") (pintype "input"))
      (node (ref "SCREW2") (pin "1") (pinfunction "1_1") (pintype "input"))
      (node (ref "SCREW3") (pin "1") (pinfunction "1_1") (pintype "input"))
      (node (ref "SCREW4") (pin "1") (pinfunction "1_1") (pintype "input"))
      (node (ref "SW1") (pin "3") (pinfunction "C_3") (pintype "unspecified"))
      (node (ref "SW1") (pin "4") (pinfunction "D_4") (pintype "unspecified"))
      (node (ref "U12") (pin "1") (pinfunction "1_1") (pintype "unspecified"))
      (node (ref "U12") (pin "2") (pinfunction "2_2") (pintype "unspecified"))
      (node (ref "U14") (pin "1") (pinfunction "1_1") (pintype "unspecified"))
      (node (ref "U14") (pin "2") (pinfunction "2_2") (pintype "unspecified"))
      (node (ref "U23") (pin "1") (pinfunction "1_1") (pintype "unspecified"))
      (node (ref "U23") (pin "2") (pinfunction "2_2") (pintype "unspecified"))
      (node (ref "U24") (pin "1") (pinfunction "1_1") (pintype "unspecified"))
      (node (ref "U24") (pin "2") (pinfunction "2_2") (pintype "unspecified"))
      (node (ref "U25") (pin "1") (pinfunction "1_1") (pintype "unspecified"))
      (node (ref "U25") (pin "2") (pinfunction "2_2") (pintype "unspecified"))
      (node (ref "U26") (pin "1") (pinfunction "1_1") (pintype "unspecified"))
      (node (ref "U26") (pin "2") (pinfunction "2_2") (pintype "unspecified"))
      (node (ref "U29") (pin "1") (pinfunction "1_1") (pintype "unspecified"))
      (node (ref "U29") (pin "2") (pinfunction "2_2") (pintype "unspecified"))
      (node (ref "U30") (pin "1") (pinfunction "1_1") (pintype "unspecified"))
      (node (ref "U30") (pin "2") (pinfunction "2_2") (pintype "unspecified"))
      (node (ref "U35") (pin "1") (pinfunction "1_1") (pintype "unspecified"))
      (node (ref "U35") (pin "10") (pinfunction "10_10") (pintype "unspecified"))
      (node (ref "U35") (pin "2") (pinfunction "2_2") (pintype "unspecified"))
      (node (ref "U35") (pin "3") (pinfunction "3_3") (pintype "unspecified"))
      (node (ref "U35") (pin "4") (pinfunction "4_4") (pintype "unspecified"))
      (node (ref "U35") (pin "5") (pinfunction "5_5") (pintype "unspecified"))
      (node (ref "U35") (pin "6") (pinfunction "6_6") (pintype "unspecified"))
      (node (ref "U35") (pin "7") (pinfunction "7_7") (pintype "unspecified"))
      (node (ref "U35") (pin "8") (pinfunction "8_8") (pintype "unspecified"))
      (node (ref "U35") (pin "9") (pinfunction "9_9") (pintype "unspecified"))
      (node (ref "USB1") (pin "4") (pinfunction "GND_4") (pintype "input"))
      (node (ref "USB1") (pin "5") (pinfunction "SHLD_5") (pintype "unspecified"))
    )
    (net (code "82") (name "Net-(LED1-+)") (class "Default")
      (node (ref "LED1") (pin "1") (pinfunction "+_1") (pintype "unspecified"))
      (node (ref "R16") (pin "2") (pinfunction "2_2") (pintype "input"))
    )
    (net (code "83") (name "Net-(LED2-+)") (class "Default")
      (node (ref "LED2") (pin "1") (pinfunction "+_1") (pintype "unspecified"))
      (node (ref "R1") (pin "2") (pinfunction "2_2") (pintype "input"))
    )
    (net (code "84") (name "Net-(LED3-+)") (class "Default")
      (node (ref "LED3") (pin "1") (pinfunction "+_1") (pintype "unspecified"))
      (node (ref "R2") (pin "2") (pinfunction "2_2") (pintype "input"))
    )
    (net (code "85") (name "Net-(LED4-+)") (class "Default")
      (node (ref "LED4") (pin "1") (pinfunction "+_1") (pintype "unspecified"))
      (node (ref "R3") (pin "2") (pinfunction "2_2") (pintype "input"))
    )
    (net (code "86") (name "Net-(LED5-+)") (class "Default")
      (node (ref "LED5") (pin "1") (pinfunction "+_1") (pintype "unspecified"))
      (node (ref "R4") (pin "2") (pinfunction "2_2") (pintype "input"))
    )
    (net (code "87") (name "Net-(SW2-A)") (class "Default")
      (node (ref "R8") (pin "2") (pinfunction "2_2") (pintype "input"))
      (node (ref "SW2") (pin "1") (pinfunction "A_1") (pintype "unspecified"))
      (node (ref "SW2") (pin "2") (pinfunction "B_2") (pintype "unspecified"))
    )
    (net (code "88") (name "Net-(SW3-A)") (class "Default")
      (node (ref "R9") (pin "2") (pinfunction "2_2") (pintype "input"))
      (node (ref "SW3") (pin "1") (pinfunction "A_1") (pintype "unspecified"))
      (node (ref "SW3") (pin "2") (pinfunction "B_2") (pintype "unspecified"))
    )
    (net (code "89") (name "Net-(SW4-A)") (class "Default")
      (node (ref "R10") (pin "2") (pinfunction "2_2") (pintype "input"))
      (node (ref "SW4") (pin "1") (pinfunction "A_1") (pintype "unspecified"))
      (node (ref "SW4") (pin "2") (pinfunction "B_2") (pintype "unspecified"))
    )
    (net (code "90") (name "Net-(SW5-A)") (class "Default")
      (node (ref "R11") (pin "2") (pinfunction "2_2") (pintype "input"))
      (node (ref "SW5") (pin "1") (pinfunction "A_1") (pintype "unspecified"))
      (node (ref "SW5") (pin "2") (pinfunction "B_2") (pintype "unspecified"))
    )
    (net (code "91") (name "unconnected-(USB1-D+-Pad3)") (class "Default")
      (node (ref "USB1") (pin "3") (pinfunction "D+_3") (pintype "input+no_connect"))
    )
    (net (code "92") (name "unconnected-(USB1-D--Pad2)") (class "Default")
      (node (ref "USB1") (pin "2") (pinfunction "D-_2") (pintype "input+no_connect"))
    )
  )
)
